# flightComputerD.net
KiCad netlist of a schematic drawn in EAGLE
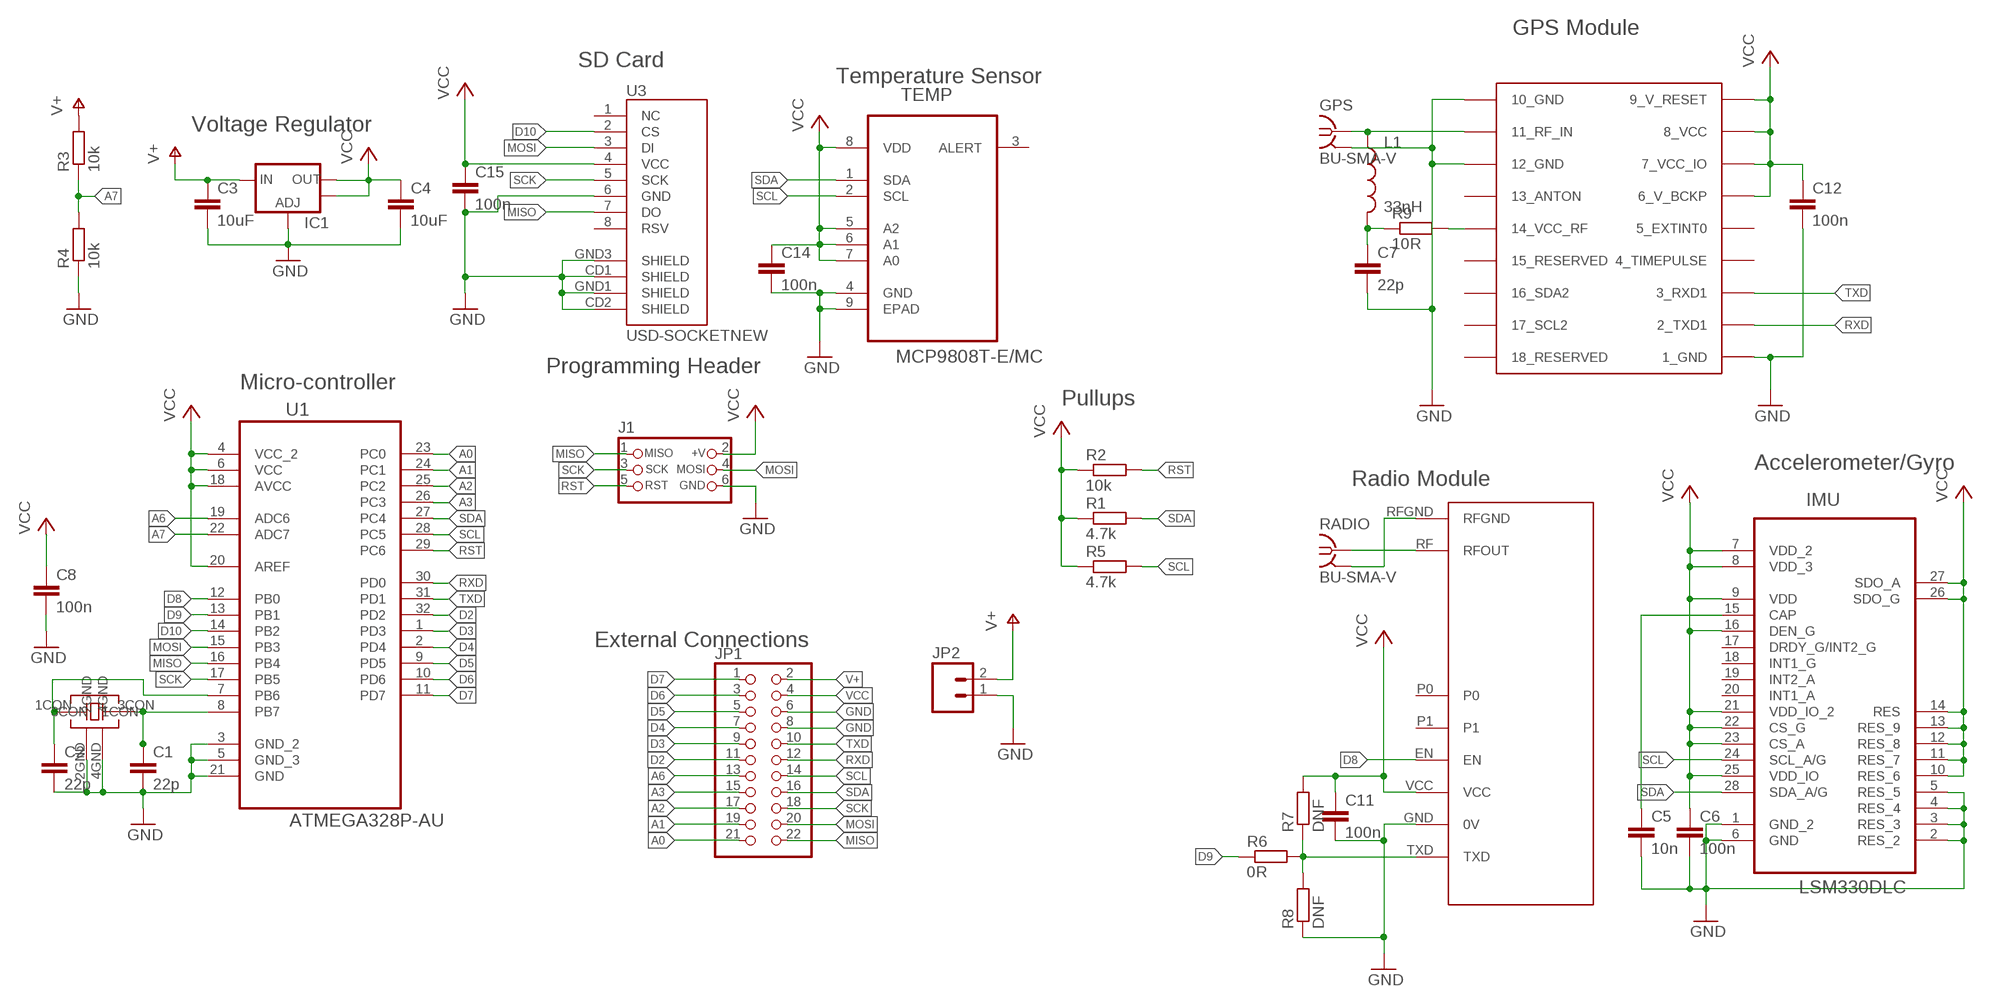
[diagram p0: schematic, sheet 1]

(export (version "E")
  (design (tool "Eeschema 10.0.6"))
  (components
    (comp (ref "C1")
      (value "22p")
      (footprint "eagle-import:C0603")
      (libsource (lib "eagle-import") (part "C-EUC0603"))
    )
    (comp (ref "C2")
      (value "22p")
      (footprint "eagle-import:C0603")
      (libsource (lib "eagle-import") (part "C-EUC0603"))
    )
    (comp (ref "C3")
      (value "10uF")
      (footprint "eagle-import:C0603")
      (libsource (lib "eagle-import") (part "C-EUC0603"))
    )
    (comp (ref "C4")
      (value "10uF")
      (footprint "eagle-import:C0603")
      (libsource (lib "eagle-import") (part "C-EUC0603"))
    )
    (comp (ref "C5")
      (value "10n")
      (footprint "eagle-import:C0603")
      (libsource (lib "eagle-import") (part "C-EUC0603"))
    )
    (comp (ref "C6")
      (value "100n")
      (footprint "eagle-import:C0603")
      (libsource (lib "eagle-import") (part "C-EUC0603"))
    )
    (comp (ref "C7")
      (value "22p")
      (footprint "eagle-import:C0603")
      (libsource (lib "eagle-import") (part "C-EUC0603"))
    )
    (comp (ref "C8")
      (value "100n")
      (footprint "eagle-import:C0603")
      (libsource (lib "eagle-import") (part "C-EUC0603"))
    )
    (comp (ref "C11")
      (value "100n")
      (footprint "eagle-import:C0603")
      (libsource (lib "eagle-import") (part "C-EUC0603"))
    )
    (comp (ref "C12")
      (value "100n")
      (footprint "eagle-import:C0603")
      (libsource (lib "eagle-import") (part "C-EUC0603"))
    )
    (comp (ref "C14")
      (value "100n")
      (footprint "eagle-import:C0603")
      (libsource (lib "eagle-import") (part "C-EUC0603"))
    )
    (comp (ref "C15")
      (value "100n")
      (footprint "eagle-import:C0603")
      (libsource (lib "eagle-import") (part "C-EUC0603"))
    )
    (comp (ref "GPS")
      (value "BU-SMA-V")
      (footprint "eagle-import:BU-SMA-V")
      (fields (field (name "OC_FARNELL") "2144531"))
      (libsource (lib "eagle-import") (part "BU-SMA-V"))
    )
    (comp (ref "IC1")
      (value "V_REG_LM1117SOT223")
      (footprint "eagle-import:SOT223")
      (libsource (lib "eagle-import") (part "V_REG_LM1117SOT223"))
    )
    (comp (ref "IMU")
      (value "LSM330DLC")
      (footprint "eagle-import:LGA28R50P6X8_400X500X110")
      (libsource (lib "eagle-import") (part "LSM330DLC"))
    )
    (comp (ref "J1")
      (value "CON_HEADER_PRG_AVR_ICSP-PTH")
      (footprint "eagle-import:HEADER_PRG_2X03")
      (libsource (lib "eagle-import") (part "CON_HEADER_PRG_AVR_ICSP-PTH"))
    )
    (comp (ref "JP1")
      (value "PINHD-2X11")
      (footprint "eagle-import:2X11")
      (libsource (lib "eagle-import") (part "PINHD-2X11"))
    )
    (comp (ref "JP2")
      (value "M02PTH")
      (footprint "eagle-import:1X02")
      (libsource (lib "eagle-import") (part "M02PTH"))
    )
    (comp (ref "L1")
      (value "33nH")
      (footprint "eagle-import:0603")
      (libsource (lib "eagle-import") (part "INDUCTOR0603"))
    )
    (comp (ref "R1")
      (value "4.7k")
      (footprint "eagle-import:R0603")
      (libsource (lib "eagle-import") (part "R-EU_R0603"))
    )
    (comp (ref "R2")
      (value "10k")
      (footprint "eagle-import:R0603")
      (libsource (lib "eagle-import") (part "R-EU_R0603"))
    )
    (comp (ref "R3")
      (value "10k")
      (footprint "eagle-import:R0603")
      (libsource (lib "eagle-import") (part "R-EU_R0603"))
    )
    (comp (ref "R4")
      (value "10k")
      (footprint "eagle-import:R0603")
      (libsource (lib "eagle-import") (part "R-EU_R0603"))
    )
    (comp (ref "R5")
      (value "4.7k")
      (footprint "eagle-import:R0603")
      (libsource (lib "eagle-import") (part "R-EU_R0603"))
    )
    (comp (ref "R6")
      (value "0R")
      (footprint "eagle-import:R0603")
      (libsource (lib "eagle-import") (part "R-EU_R0603"))
    )
    (comp (ref "R7")
      (value "DNF")
      (footprint "eagle-import:R0603")
      (libsource (lib "eagle-import") (part "R-EU_R0603"))
    )
    (comp (ref "R8")
      (value "DNF")
      (footprint "eagle-import:R0603")
      (libsource (lib "eagle-import") (part "R-EU_R0603"))
    )
    (comp (ref "R9")
      (value "10R")
      (footprint "eagle-import:R0603")
      (libsource (lib "eagle-import") (part "R-EU_R0603"))
    )
    (comp (ref "RADIO")
      (value "BU-SMA-V")
      (footprint "eagle-import:BU-SMA-V")
      (fields (field (name "OC_FARNELL") "2144531"))
      (libsource (lib "eagle-import") (part "BU-SMA-V"))
    )
    (comp (ref "TEMP")
      (value "MCP9808T-E/MC")
      (footprint "eagle-import:DFN300X200X100-9N")
      (libsource (lib "eagle-import") (part "MCP9808T-E/MC"))
    )
    (comp (ref "U$1")
      (value "CRYSTAL")
      (footprint "eagle-import:CRYSTAL")
      (libsource (lib "eagle-import") (part "CRYSTAL"))
    )
    (comp (ref "U$4")
      (value "UBLOX_MAX")
      (footprint "eagle-import:UBLOX_MAX")
      (libsource (lib "eagle-import") (part "UBLOX_MAX"))
    )
    (comp (ref "U$6")
      (value "RADIOMETRIX-MTX2")
      (footprint "eagle-import:RADIOMETRIX-MTX2")
      (libsource (lib "eagle-import") (part "RADIOMETRIX-MTX2"))
    )
    (comp (ref "U1")
      (value "ATMEGA328P-AU")
      (footprint "eagle-import:QFP80P900X900X120-32N")
      (libsource (lib "eagle-import") (part "ATMEGA328P-AU"))
    )
    (comp (ref "U3")
      (value "USD-SOCKETNEW")
      (footprint "eagle-import:MICRO-SD-SOCKET-PP")
      (libsource (lib "eagle-import") (part "USD-SOCKETNEW"))
    )
  )
  (nets
    (net (code "1") (name "A0") (class "Default")
      (node (ref "JP1") (pin "21") (pinfunction "21_21") (pintype "passive"))
      (node (ref "U1") (pin "23") (pinfunction "PC0_23") (pintype "bidirectional"))
    )
    (net (code "2") (name "A1") (class "Default")
      (node (ref "JP1") (pin "19") (pinfunction "19_19") (pintype "passive"))
      (node (ref "U1") (pin "24") (pinfunction "PC1_24") (pintype "bidirectional"))
    )
    (net (code "3") (name "A2") (class "Default")
      (node (ref "JP1") (pin "17") (pinfunction "17_17") (pintype "passive"))
      (node (ref "U1") (pin "25") (pinfunction "PC2_25") (pintype "bidirectional"))
    )
    (net (code "4") (name "A3") (class "Default")
      (node (ref "JP1") (pin "15") (pinfunction "15_15") (pintype "passive"))
      (node (ref "U1") (pin "26") (pinfunction "PC3_26") (pintype "bidirectional"))
    )
    (net (code "5") (name "A6") (class "Default")
      (node (ref "JP1") (pin "13") (pinfunction "13_13") (pintype "passive"))
      (node (ref "U1") (pin "19") (pinfunction "ADC6_19") (pintype "input"))
    )
    (net (code "6") (name "A7") (class "Default")
      (node (ref "R3") (pin "1") (pinfunction "1_1") (pintype "passive"))
      (node (ref "R4") (pin "2") (pinfunction "2_2") (pintype "passive"))
      (node (ref "U1") (pin "22") (pinfunction "ADC7_22") (pintype "input"))
    )
    (net (code "7") (name "D2") (class "Default")
      (node (ref "JP1") (pin "11") (pinfunction "11_11") (pintype "passive"))
      (node (ref "U1") (pin "32") (pinfunction "PD2_32") (pintype "bidirectional"))
    )
    (net (code "8") (name "D3") (class "Default")
      (node (ref "JP1") (pin "9") (pinfunction "9_9") (pintype "passive"))
      (node (ref "U1") (pin "1") (pinfunction "PD3_1") (pintype "bidirectional"))
    )
    (net (code "9") (name "D4") (class "Default")
      (node (ref "JP1") (pin "7") (pinfunction "7_7") (pintype "passive"))
      (node (ref "U1") (pin "2") (pinfunction "PD4_2") (pintype "bidirectional"))
    )
    (net (code "10") (name "D5") (class "Default")
      (node (ref "JP1") (pin "5") (pinfunction "5_5") (pintype "passive"))
      (node (ref "U1") (pin "9") (pinfunction "PD5_9") (pintype "bidirectional"))
    )
    (net (code "11") (name "D6") (class "Default")
      (node (ref "JP1") (pin "3") (pinfunction "3_3") (pintype "passive"))
      (node (ref "U1") (pin "10") (pinfunction "PD6_10") (pintype "bidirectional"))
    )
    (net (code "12") (name "D7") (class "Default")
      (node (ref "JP1") (pin "1") (pinfunction "1_1") (pintype "passive"))
      (node (ref "U1") (pin "11") (pinfunction "PD7_11") (pintype "bidirectional"))
    )
    (net (code "13") (name "D8") (class "Default")
      (node (ref "U$6") (pin "EN") (pinfunction "EN_EN") (pintype "bidirectional"))
      (node (ref "U1") (pin "12") (pinfunction "PB0_12") (pintype "bidirectional"))
    )
    (net (code "14") (name "D9") (class "Default")
      (node (ref "R6") (pin "1") (pinfunction "1_1") (pintype "passive"))
      (node (ref "U1") (pin "13") (pinfunction "PB1_13") (pintype "bidirectional"))
    )
    (net (code "15") (name "D10") (class "Default")
      (node (ref "U1") (pin "14") (pinfunction "PB2_14") (pintype "bidirectional"))
      (node (ref "U3") (pin "2") (pinfunction "CS_2") (pintype "bidirectional"))
    )
    (net (code "16") (name "GND") (class "Default")
      (node (ref "C1") (pin "2") (pinfunction "2_2") (pintype "passive"))
      (node (ref "C11") (pin "2") (pinfunction "2_2") (pintype "passive"))
      (node (ref "C12") (pin "2") (pinfunction "2_2") (pintype "passive"))
      (node (ref "C14") (pin "2") (pinfunction "2_2") (pintype "passive"))
      (node (ref "C15") (pin "2") (pinfunction "2_2") (pintype "passive"))
      (node (ref "C2") (pin "2") (pinfunction "2_2") (pintype "passive"))
      (node (ref "C3") (pin "2") (pinfunction "2_2") (pintype "passive"))
      (node (ref "C4") (pin "2") (pinfunction "2_2") (pintype "passive"))
      (node (ref "C5") (pin "2") (pinfunction "2_2") (pintype "passive"))
      (node (ref "C6") (pin "2") (pinfunction "2_2") (pintype "passive"))
      (node (ref "C7") (pin "2") (pinfunction "2_2") (pintype "passive"))
      (node (ref "C8") (pin "2") (pinfunction "2_2") (pintype "passive"))
      (node (ref "GPS") (pin "2") (pinfunction "2_2") (pintype "passive"))
      (node (ref "GPS") (pin "3") (pinfunction "2_3") (pintype "passive"))
      (node (ref "GPS") (pin "4") (pinfunction "2_4") (pintype "passive"))
      (node (ref "GPS") (pin "5") (pinfunction "2_5") (pintype "passive"))
      (node (ref "IC1") (pin "1") (pinfunction "ADJ_1") (pintype "input"))
      (node (ref "IMU") (pin "1") (pinfunction "GND_2_1") (pintype "power_in"))
      (node (ref "IMU") (pin "2") (pinfunction "RES_2_2") (pintype "passive"))
      (node (ref "IMU") (pin "3") (pinfunction "RES_3_3") (pintype "passive"))
      (node (ref "IMU") (pin "4") (pinfunction "RES_4_4") (pintype "passive"))
      (node (ref "IMU") (pin "5") (pinfunction "RES_5_5") (pintype "passive"))
      (node (ref "IMU") (pin "6") (pinfunction "GND_6") (pintype "power_in"))
      (node (ref "J1") (pin "6") (pinfunction "GND_6") (pintype "passive"))
      (node (ref "JP1") (pin "6") (pinfunction "6_6") (pintype "passive"))
      (node (ref "JP1") (pin "8") (pinfunction "8_8") (pintype "passive"))
      (node (ref "JP2") (pin "1") (pinfunction "1_1") (pintype "passive"))
      (node (ref "R4") (pin "1") (pinfunction "1_1") (pintype "passive"))
      (node (ref "R8") (pin "1") (pinfunction "1_1") (pintype "passive"))
      (node (ref "TEMP") (pin "4") (pinfunction "GND_4") (pintype "power_in"))
      (node (ref "TEMP") (pin "9") (pinfunction "EPAD_9") (pintype "passive"))
      (node (ref "U$1") (pin "2GND") (pinfunction "2GND_2GND") (pintype "bidirectional"))
      (node (ref "U$1") (pin "4GND") (pinfunction "4GND_4GND") (pintype "bidirectional"))
      (node (ref "U$4") (pin "10_GND") (pinfunction "10_GND_10_GND") (pintype "power_in"))
      (node (ref "U$4") (pin "12_GND") (pinfunction "12_GND_12_GND") (pintype "power_in"))
      (node (ref "U$4") (pin "1_GND") (pinfunction "1_GND_1_GND") (pintype "power_in"))
      (node (ref "U$6") (pin "GND") (pinfunction "0V_GND") (pintype "bidirectional"))
      (node (ref "U1") (pin "21") (pinfunction "GND_21") (pintype "passive"))
      (node (ref "U1") (pin "3") (pinfunction "GND_2_3") (pintype "passive"))
      (node (ref "U1") (pin "5") (pinfunction "GND_3_5") (pintype "passive"))
      (node (ref "U3") (pin "6") (pinfunction "GND_6") (pintype "bidirectional"))
      (node (ref "U3") (pin "CD1") (pinfunction "SHIELD_CD1") (pintype "bidirectional"))
      (node (ref "U3") (pin "CD2") (pinfunction "SHIELD_CD2") (pintype "bidirectional"))
      (node (ref "U3") (pin "GND1") (pinfunction "SHIELD_GND1") (pintype "bidirectional"))
      (node (ref "U3") (pin "GND3") (pinfunction "SHIELD_GND3") (pintype "bidirectional"))
    )
    (net (code "17") (name "MISO") (class "Default")
      (node (ref "J1") (pin "1") (pinfunction "MISO_1") (pintype "passive"))
      (node (ref "JP1") (pin "22") (pinfunction "22_22") (pintype "passive"))
      (node (ref "U1") (pin "16") (pinfunction "PB4_16") (pintype "bidirectional"))
      (node (ref "U3") (pin "7") (pinfunction "DO_7") (pintype "bidirectional"))
    )
    (net (code "18") (name "MOSI") (class "Default")
      (node (ref "J1") (pin "4") (pinfunction "MOSI_4") (pintype "passive"))
      (node (ref "JP1") (pin "20") (pinfunction "20_20") (pintype "passive"))
      (node (ref "U1") (pin "15") (pinfunction "PB3_15") (pintype "bidirectional"))
      (node (ref "U3") (pin "3") (pinfunction "DI_3") (pintype "bidirectional"))
    )
    (net (code "19") (name "Net-(C7-Pad1)") (class "Default")
      (node (ref "C7") (pin "1") (pinfunction "1_1") (pintype "passive"))
      (node (ref "L1") (pin "2") (pinfunction "2_2") (pintype "passive"))
      (node (ref "R9") (pin "1") (pinfunction "1_1") (pintype "passive"))
    )
    (net (code "20") (name "Net-(GPS-Pad1)") (class "Default")
      (node (ref "GPS") (pin "1") (pinfunction "1_1") (pintype "passive"))
      (node (ref "L1") (pin "1") (pinfunction "1_1") (pintype "passive"))
      (node (ref "U$4") (pin "11_RF_IN") (pinfunction "11_RF_IN_11_RF_IN") (pintype "bidirectional"))
    )
    (net (code "21") (name "Net-(IMU-CAP)") (class "Default")
      (node (ref "C5") (pin "1") (pinfunction "1_1") (pintype "passive"))
      (node (ref "IMU") (pin "15") (pinfunction "CAP_15") (pintype "passive"))
    )
    (net (code "22") (name "Net-(R6-Pad2)") (class "Default")
      (node (ref "R6") (pin "2") (pinfunction "2_2") (pintype "passive"))
      (node (ref "R7") (pin "1") (pinfunction "1_1") (pintype "passive"))
      (node (ref "R8") (pin "2") (pinfunction "2_2") (pintype "passive"))
      (node (ref "U$6") (pin "TXD") (pinfunction "TXD_TXD") (pintype "bidirectional"))
    )
    (net (code "23") (name "Net-(R9-Pad2)") (class "Default")
      (node (ref "R9") (pin "2") (pinfunction "2_2") (pintype "passive"))
      (node (ref "U$4") (pin "14_VCC_RF") (pinfunction "14_VCC_RF_14_VCC_RF") (pintype "bidirectional"))
    )
    (net (code "24") (name "Net-(RADIO-2-Pad3)") (class "Default")
      (node (ref "RADIO") (pin "2") (pinfunction "2_2") (pintype "passive"))
      (node (ref "RADIO") (pin "3") (pinfunction "2_3") (pintype "passive"))
      (node (ref "RADIO") (pin "4") (pinfunction "2_4") (pintype "passive"))
      (node (ref "RADIO") (pin "5") (pinfunction "2_5") (pintype "passive"))
      (node (ref "U$6") (pin "RFGND") (pinfunction "RFGND_RFGND") (pintype "bidirectional"))
    )
    (net (code "25") (name "Net-(U$6-RFOUT)") (class "Default")
      (node (ref "RADIO") (pin "1") (pinfunction "1_1") (pintype "passive"))
      (node (ref "U$6") (pin "RF") (pinfunction "RFOUT_RF") (pintype "bidirectional"))
    )
    (net (code "26") (name "Net-(U1-PB6)") (class "Default")
      (node (ref "C2") (pin "1") (pinfunction "1_1") (pintype "passive"))
      (node (ref "U$1") (pin "1CON") (pinfunction "1CON_1CON") (pintype "bidirectional"))
      (node (ref "U1") (pin "7") (pinfunction "PB6_7") (pintype "bidirectional"))
    )
    (net (code "27") (name "Net-(U1-PB7)") (class "Default")
      (node (ref "C1") (pin "1") (pinfunction "1_1") (pintype "passive"))
      (node (ref "U$1") (pin "3CON") (pinfunction "3CON_3CON") (pintype "bidirectional"))
      (node (ref "U1") (pin "8") (pinfunction "PB7_8") (pintype "bidirectional"))
    )
    (net (code "28") (name "RST") (class "Default")
      (node (ref "J1") (pin "5") (pinfunction "RST_5") (pintype "passive"))
      (node (ref "R2") (pin "2") (pinfunction "2_2") (pintype "passive"))
      (node (ref "U1") (pin "29") (pinfunction "PC6_29") (pintype "bidirectional"))
    )
    (net (code "29") (name "RXD") (class "Default")
      (node (ref "JP1") (pin "12") (pinfunction "12_12") (pintype "passive"))
      (node (ref "U$4") (pin "2_TXD1") (pinfunction "2_TXD1_2_TXD1") (pintype "bidirectional"))
      (node (ref "U1") (pin "30") (pinfunction "PD0_30") (pintype "bidirectional"))
    )
    (net (code "30") (name "SCK") (class "Default")
      (node (ref "J1") (pin "3") (pinfunction "SCK_3") (pintype "passive"))
      (node (ref "JP1") (pin "18") (pinfunction "18_18") (pintype "passive"))
      (node (ref "U1") (pin "17") (pinfunction "PB5_17") (pintype "bidirectional"))
      (node (ref "U3") (pin "5") (pinfunction "SCK_5") (pintype "bidirectional"))
    )
    (net (code "31") (name "SCL") (class "Default")
      (node (ref "IMU") (pin "24") (pinfunction "SCL_A/G_24") (pintype "passive"))
      (node (ref "JP1") (pin "14") (pinfunction "14_14") (pintype "passive"))
      (node (ref "R5") (pin "2") (pinfunction "2_2") (pintype "passive"))
      (node (ref "TEMP") (pin "2") (pinfunction "SCL_2") (pintype "input"))
      (node (ref "U1") (pin "28") (pinfunction "PC5_28") (pintype "bidirectional"))
    )
    (net (code "32") (name "SDA") (class "Default")
      (node (ref "IMU") (pin "28") (pinfunction "SDA_A/G_28") (pintype "passive"))
      (node (ref "JP1") (pin "16") (pinfunction "16_16") (pintype "passive"))
      (node (ref "R1") (pin "2") (pinfunction "2_2") (pintype "passive"))
      (node (ref "TEMP") (pin "1") (pinfunction "SDA_1") (pintype "input"))
      (node (ref "U1") (pin "27") (pinfunction "PC4_27") (pintype "bidirectional"))
    )
    (net (code "33") (name "TXD") (class "Default")
      (node (ref "JP1") (pin "10") (pinfunction "10_10") (pintype "passive"))
      (node (ref "U$4") (pin "3_RXD1") (pinfunction "3_RXD1_3_RXD1") (pintype "bidirectional"))
      (node (ref "U1") (pin "31") (pinfunction "PD1_31") (pintype "bidirectional"))
    )
    (net (code "34") (name "V+") (class "Default")
      (node (ref "C3") (pin "1") (pinfunction "1_1") (pintype "passive"))
      (node (ref "IC1") (pin "3") (pinfunction "IN_3") (pintype "input"))
      (node (ref "JP1") (pin "2") (pinfunction "2_2") (pintype "passive"))
      (node (ref "JP2") (pin "2") (pinfunction "2_2") (pintype "passive"))
      (node (ref "R3") (pin "2") (pinfunction "2_2") (pintype "passive"))
    )
    (net (code "35") (name "VCC") (class "Default")
      (node (ref "C11") (pin "1") (pinfunction "1_1") (pintype "passive"))
      (node (ref "C12") (pin "1") (pinfunction "1_1") (pintype "passive"))
      (node (ref "C14") (pin "1") (pinfunction "1_1") (pintype "passive"))
      (node (ref "C15") (pin "1") (pinfunction "1_1") (pintype "passive"))
      (node (ref "C4") (pin "1") (pinfunction "1_1") (pintype "passive"))
      (node (ref "C6") (pin "1") (pinfunction "1_1") (pintype "passive"))
      (node (ref "C8") (pin "1") (pinfunction "1_1") (pintype "passive"))
      (node (ref "IC1") (pin "2") (pinfunction "OUT_2") (pintype "output"))
      (node (ref "IC1") (pin "4") (pinfunction "OUT_4") (pintype "output"))
      (node (ref "IMU") (pin "10") (pinfunction "RES_6_10") (pintype "passive"))
      (node (ref "IMU") (pin "11") (pinfunction "RES_7_11") (pintype "passive"))
      (node (ref "IMU") (pin "12") (pinfunction "RES_8_12") (pintype "passive"))
      (node (ref "IMU") (pin "13") (pinfunction "RES_9_13") (pintype "passive"))
      (node (ref "IMU") (pin "14") (pinfunction "RES_14") (pintype "passive"))
      (node (ref "IMU") (pin "16") (pinfunction "DEN_G_16") (pintype "passive"))
      (node (ref "IMU") (pin "21") (pinfunction "VDD_IO_2_21") (pintype "power_in"))
      (node (ref "IMU") (pin "22") (pinfunction "CS_G_22") (pintype "passive"))
      (node (ref "IMU") (pin "23") (pinfunction "CS_A_23") (pintype "passive"))
      (node (ref "IMU") (pin "25") (pinfunction "VDD_IO_25") (pintype "power_in"))
      (node (ref "IMU") (pin "26") (pinfunction "SDO_G_26") (pintype "passive"))
      (node (ref "IMU") (pin "27") (pinfunction "SDO_A_27") (pintype "passive"))
      (node (ref "IMU") (pin "7") (pinfunction "VDD_2_7") (pintype "power_in"))
      (node (ref "IMU") (pin "8") (pinfunction "VDD_3_8") (pintype "power_in"))
      (node (ref "IMU") (pin "9") (pinfunction "VDD_9") (pintype "power_in"))
      (node (ref "J1") (pin "2") (pinfunction "+V_2") (pintype "passive"))
      (node (ref "JP1") (pin "4") (pinfunction "4_4") (pintype "passive"))
      (node (ref "R1") (pin "1") (pinfunction "1_1") (pintype "passive"))
      (node (ref "R2") (pin "1") (pinfunction "1_1") (pintype "passive"))
      (node (ref "R5") (pin "1") (pinfunction "1_1") (pintype "passive"))
      (node (ref "R7") (pin "2") (pinfunction "2_2") (pintype "passive"))
      (node (ref "TEMP") (pin "5") (pinfunction "A2_5") (pintype "input"))
      (node (ref "TEMP") (pin "6") (pinfunction "A1_6") (pintype "input"))
      (node (ref "TEMP") (pin "7") (pinfunction "A0_7") (pintype "input"))
      (node (ref "TEMP") (pin "8") (pinfunction "VDD_8") (pintype "power_in"))
      (node (ref "U$4") (pin "6_V_BCKP") (pinfunction "6_V_BCKP_6_V_BCKP") (pintype "bidirectional"))
      (node (ref "U$4") (pin "7_VCC_IO") (pinfunction "7_VCC_IO_7_VCC_IO") (pintype "power_in"))
      (node (ref "U$4") (pin "8_VCC") (pinfunction "8_VCC_8_VCC") (pintype "power_in"))
      (node (ref "U$4") (pin "9_V_RESET") (pinfunction "9_V_RESET_9_V_RESET") (pintype "power_in"))
      (node (ref "U$6") (pin "VCC") (pinfunction "VCC_VCC") (pintype "bidirectional"))
      (node (ref "U1") (pin "18") (pinfunction "AVCC_18") (pintype "power_in"))
      (node (ref "U1") (pin "20") (pinfunction "AREF_20") (pintype "input"))
      (node (ref "U1") (pin "4") (pinfunction "VCC_2_4") (pintype "power_in"))
      (node (ref "U1") (pin "6") (pinfunction "VCC_6") (pintype "power_in"))
      (node (ref "U3") (pin "4") (pinfunction "VCC_4") (pintype "bidirectional"))
    )
    (net (code "36") (name "unconnected-(IMU-DRDY_G{slash}INT2_G-Pad17)") (class "Default")
      (node (ref "IMU") (pin "17") (pinfunction "DRDY_G/INT2_G_17") (pintype "passive"))
    )
    (net (code "37") (name "unconnected-(IMU-INT1_A-Pad20)") (class "Default")
      (node (ref "IMU") (pin "20") (pinfunction "INT1_A_20") (pintype "passive"))
    )
    (net (code "38") (name "unconnected-(IMU-INT1_G-Pad18)") (class "Default")
      (node (ref "IMU") (pin "18") (pinfunction "INT1_G_18") (pintype "passive"))
    )
    (net (code "39") (name "unconnected-(IMU-INT2_A-Pad19)") (class "Default")
      (node (ref "IMU") (pin "19") (pinfunction "INT2_A_19") (pintype "passive"))
    )
    (net (code "40") (name "unconnected-(TEMP-ALERT-Pad3)") (class "Default")
      (node (ref "TEMP") (pin "3") (pinfunction "ALERT_3") (pintype "output"))
    )
    (net (code "41") (name "unconnected-(U$4-Pad4_TIMEPULSE)") (class "Default")
      (node (ref "U$4") (pin "4_TIMEPULSE") (pinfunction "4_TIMEPULSE_4_TIMEPULSE") (pintype "bidirectional"))
    )
    (net (code "42") (name "unconnected-(U$4-Pad5_EXTINT0)") (class "Default")
      (node (ref "U$4") (pin "5_EXTINT0") (pinfunction "5_EXTINT0_5_EXTINT0") (pintype "bidirectional"))
    )
    (net (code "43") (name "unconnected-(U$4-Pad13_ANTON)") (class "Default")
      (node (ref "U$4") (pin "13_ANTON") (pinfunction "13_ANTON_13_ANTON") (pintype "bidirectional"))
    )
    (net (code "44") (name "unconnected-(U$4-Pad15_RESERVED)") (class "Default")
      (node (ref "U$4") (pin "15_RESERVED") (pinfunction "15_RESERVED_15_RESERVED") (pintype "bidirectional"))
    )
    (net (code "45") (name "unconnected-(U$4-Pad16_SDA2)") (class "Default")
      (node (ref "U$4") (pin "16_SDA2") (pinfunction "16_SDA2_16_SDA2") (pintype "bidirectional"))
    )
    (net (code "46") (name "unconnected-(U$4-Pad17_SCL2)") (class "Default")
      (node (ref "U$4") (pin "17_SCL2") (pinfunction "17_SCL2_17_SCL2") (pintype "bidirectional"))
    )
    (net (code "47") (name "unconnected-(U$4-Pad18_RESERVED)") (class "Default")
      (node (ref "U$4") (pin "18_RESERVED") (pinfunction "18_RESERVED_18_RESERVED") (pintype "bidirectional"))
    )
    (net (code "48") (name "unconnected-(U$6-PadP0)") (class "Default")
      (node (ref "U$6") (pin "P0") (pinfunction "P0_P0") (pintype "bidirectional"))
    )
    (net (code "49") (name "unconnected-(U$6-PadP1)") (class "Default")
      (node (ref "U$6") (pin "P1") (pinfunction "P1_P1") (pintype "bidirectional"))
    )
    (net (code "50") (name "unconnected-(U3-NC-Pad1)") (class "Default")
      (node (ref "U3") (pin "1") (pinfunction "NC_1") (pintype "bidirectional"))
    )
    (net (code "51") (name "unconnected-(U3-RSV-Pad8)") (class "Default")
      (node (ref "U3") (pin "8") (pinfunction "RSV_8") (pintype "bidirectional"))
    )
  )
)
